# PCB-TLY-JACK.net
KiCad netlist of a schematic drawn in EAGLE
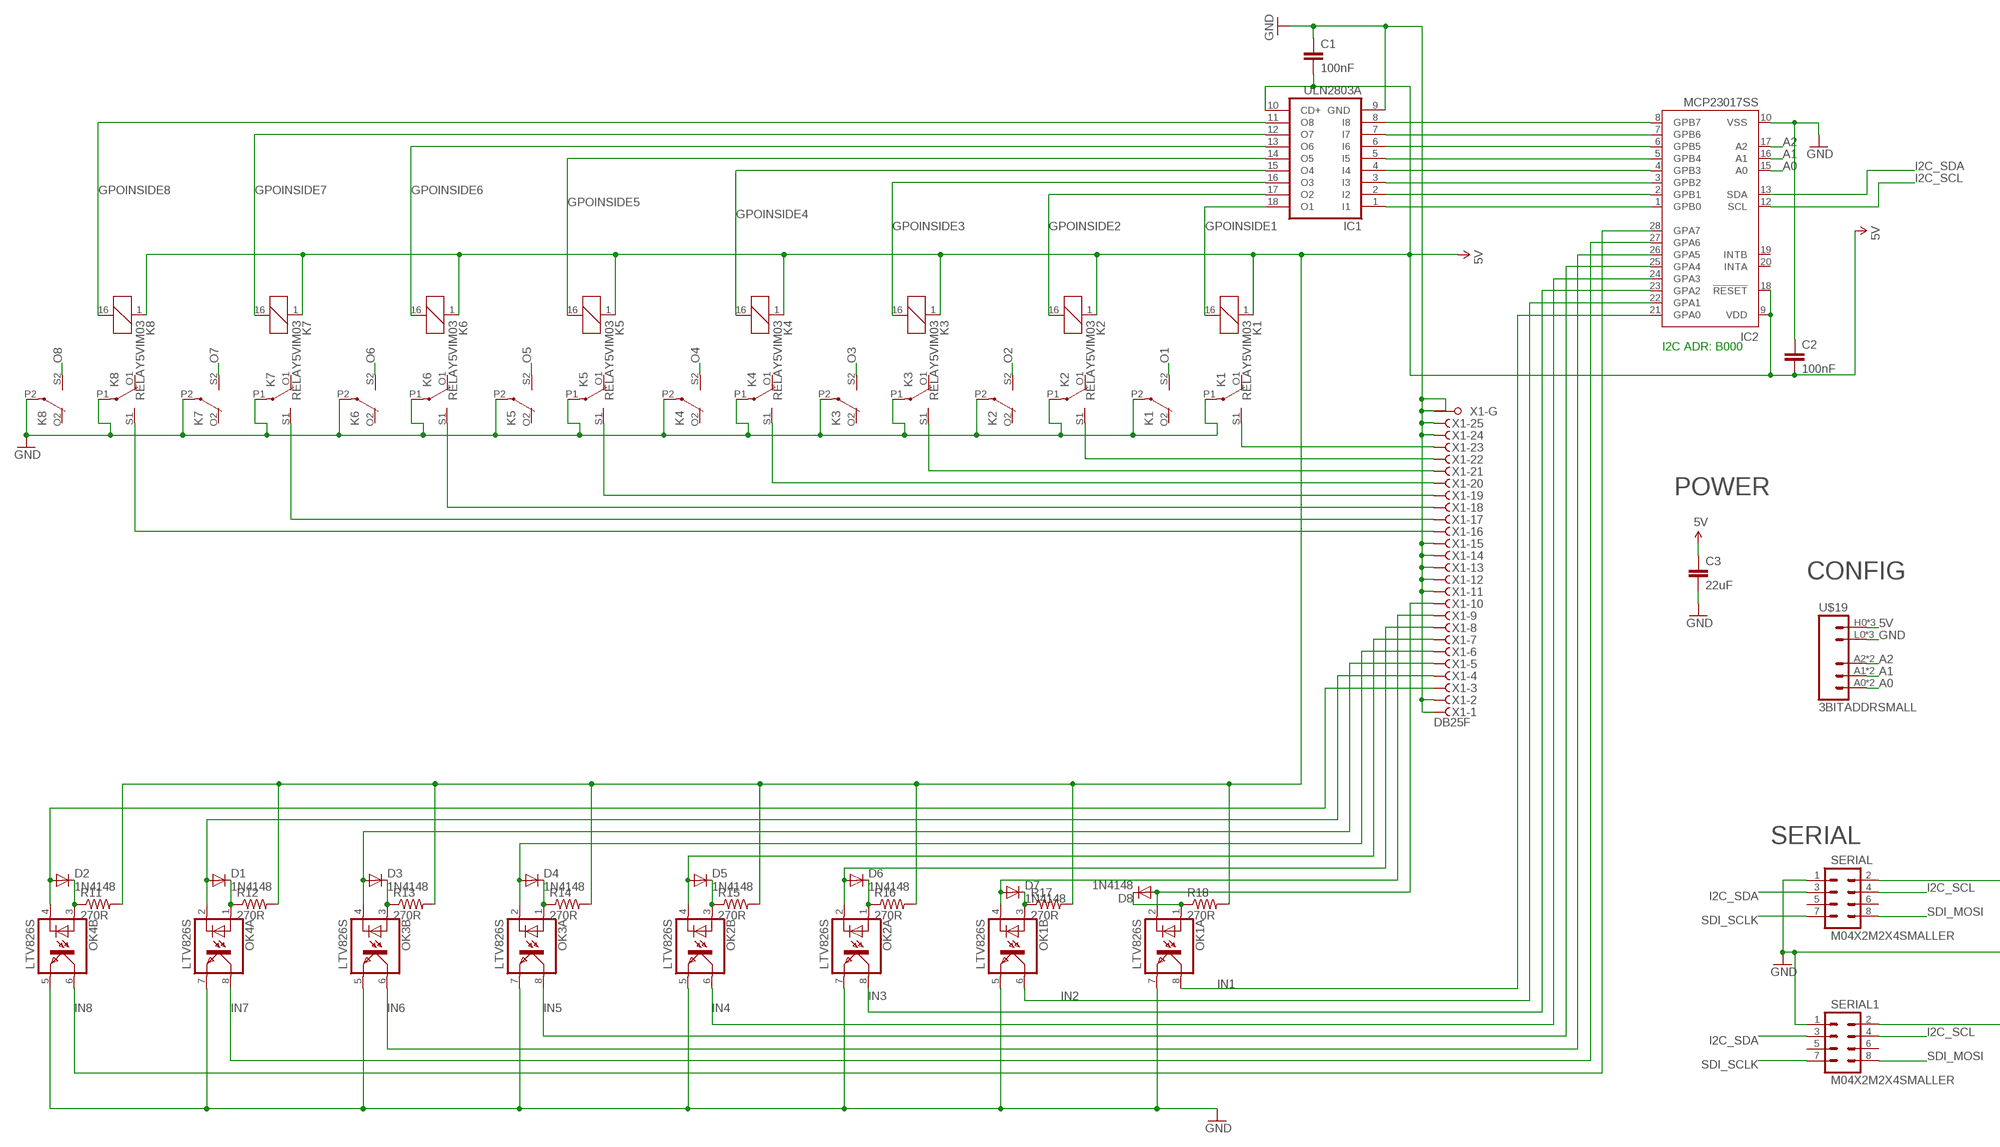
[diagram p0: schematic, sheet 1, part 1 of 2]
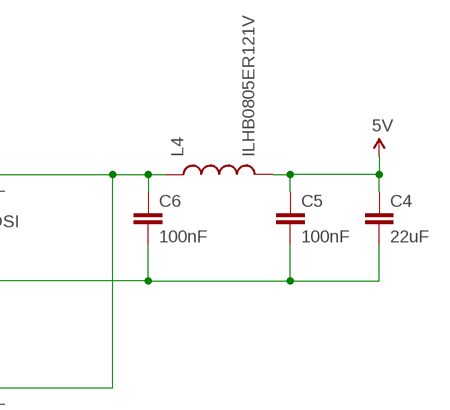
[diagram p1: schematic, sheet 1, part 2 of 2]

(export (version "E")
  (design (tool "Eeschema 10.0.6"))
  (components
    (comp (ref "C1")
      (value "100nF")
      (footprint "eagle-import:0603-CAP")
      (libsource (lib "eagle-import") (part "CAP0603-CAP"))
    )
    (comp (ref "C2")
      (value "100nF")
      (footprint "eagle-import:0603-CAP")
      (libsource (lib "eagle-import") (part "CAP0603-CAP"))
    )
    (comp (ref "C3")
      (value "22uF")
      (footprint "eagle-import:0805")
      (libsource (lib "eagle-import") (part "CAP0805"))
    )
    (comp (ref "C4")
      (value "22uF")
      (footprint "eagle-import:0805")
      (libsource (lib "eagle-import") (part "CAP0805"))
    )
    (comp (ref "C5")
      (value "100nF")
      (footprint "eagle-import:0603-CAP")
      (libsource (lib "eagle-import") (part "CAP0603-CAP"))
    )
    (comp (ref "C6")
      (value "100nF")
      (footprint "eagle-import:0603-CAP")
      (libsource (lib "eagle-import") (part "CAP0603-CAP"))
    )
    (comp (ref "D1")
      (value "1N4148")
      (footprint "eagle-import:SOD-323")
      (libsource (lib "eagle-import") (part "DIODESOD"))
    )
    (comp (ref "D2")
      (value "1N4148")
      (footprint "eagle-import:SOD-323")
      (libsource (lib "eagle-import") (part "DIODESOD"))
    )
    (comp (ref "D3")
      (value "1N4148")
      (footprint "eagle-import:SOD-323")
      (libsource (lib "eagle-import") (part "DIODESOD"))
    )
    (comp (ref "D4")
      (value "1N4148")
      (footprint "eagle-import:SOD-323")
      (libsource (lib "eagle-import") (part "DIODESOD"))
    )
    (comp (ref "D5")
      (value "1N4148")
      (footprint "eagle-import:SOD-323")
      (libsource (lib "eagle-import") (part "DIODESOD"))
    )
    (comp (ref "D6")
      (value "1N4148")
      (footprint "eagle-import:SOD-323")
      (libsource (lib "eagle-import") (part "DIODESOD"))
    )
    (comp (ref "D7")
      (value "1N4148")
      (footprint "eagle-import:SOD-323")
      (libsource (lib "eagle-import") (part "DIODESOD"))
    )
    (comp (ref "D8")
      (value "1N4148")
      (footprint "eagle-import:SOD-323")
      (libsource (lib "eagle-import") (part "DIODESOD"))
    )
    (comp (ref "IC1")
      (value "ULN2803A")
      (footprint "eagle-import:SO18W")
      (libsource (lib "eagle-import") (part "ULN2803ASO18W"))
    )
    (comp (ref "IC2")
      (value "MCP23017SS")
      (footprint "eagle-import:SSOP28")
      (fields (field (name "MF") "MICROCHIP") (field (name "MPN") "MCP23017-E/SS"))
      (libsource (lib "eagle-import") (part "MCP23017SS"))
    )
    (comp (ref "K1")
      (value "RELAY5VIM03")
      (footprint "eagle-import:DS2Y")
      (libsource (lib "eagle-import") (part "RELAY5VIM03"))
    )
    (comp (ref "K2")
      (value "RELAY5VIM03")
      (footprint "eagle-import:DS2Y")
      (libsource (lib "eagle-import") (part "RELAY5VIM03"))
    )
    (comp (ref "K3")
      (value "RELAY5VIM03")
      (footprint "eagle-import:DS2Y")
      (libsource (lib "eagle-import") (part "RELAY5VIM03"))
    )
    (comp (ref "K4")
      (value "RELAY5VIM03")
      (footprint "eagle-import:DS2Y")
      (libsource (lib "eagle-import") (part "RELAY5VIM03"))
    )
    (comp (ref "K5")
      (value "RELAY5VIM03")
      (footprint "eagle-import:DS2Y")
      (libsource (lib "eagle-import") (part "RELAY5VIM03"))
    )
    (comp (ref "K6")
      (value "RELAY5VIM03")
      (footprint "eagle-import:DS2Y")
      (libsource (lib "eagle-import") (part "RELAY5VIM03"))
    )
    (comp (ref "K7")
      (value "RELAY5VIM03")
      (footprint "eagle-import:DS2Y")
      (libsource (lib "eagle-import") (part "RELAY5VIM03"))
    )
    (comp (ref "K8")
      (value "RELAY5VIM03")
      (footprint "eagle-import:DS2Y")
      (libsource (lib "eagle-import") (part "RELAY5VIM03"))
    )
    (comp (ref "L4")
      (value "ILHB0805ER121V")
      (footprint "eagle-import:0805")
      (libsource (lib "eagle-import") (part "INDUCTOR0805"))
    )
    (comp (ref "OK1")
      (value "LTV826S")
      (footprint "eagle-import:DIL8-SMD")
      (libsource (lib "eagle-import") (part "LTV826S"))
    )
    (comp (ref "OK2")
      (value "LTV826S")
      (footprint "eagle-import:DIL8-SMD")
      (libsource (lib "eagle-import") (part "LTV826S"))
    )
    (comp (ref "OK3")
      (value "LTV826S")
      (footprint "eagle-import:DIL8-SMD")
      (libsource (lib "eagle-import") (part "LTV826S"))
    )
    (comp (ref "OK4")
      (value "LTV826S")
      (footprint "eagle-import:DIL8-SMD")
      (libsource (lib "eagle-import") (part "LTV826S"))
    )
    (comp (ref "R11")
      (value "270R")
      (footprint "eagle-import:0603-RES")
      (libsource (lib "eagle-import") (part "RESISTOR0603-RES"))
    )
    (comp (ref "R12")
      (value "270R")
      (footprint "eagle-import:0603-RES")
      (libsource (lib "eagle-import") (part "RESISTOR0603-RES"))
    )
    (comp (ref "R13")
      (value "270R")
      (footprint "eagle-import:0603-RES")
      (libsource (lib "eagle-import") (part "RESISTOR0603-RES"))
    )
    (comp (ref "R14")
      (value "270R")
      (footprint "eagle-import:0603-RES")
      (libsource (lib "eagle-import") (part "RESISTOR0603-RES"))
    )
    (comp (ref "R15")
      (value "270R")
      (footprint "eagle-import:0603-RES")
      (libsource (lib "eagle-import") (part "RESISTOR0603-RES"))
    )
    (comp (ref "R16")
      (value "270R")
      (footprint "eagle-import:0603-RES")
      (libsource (lib "eagle-import") (part "RESISTOR0603-RES"))
    )
    (comp (ref "R17")
      (value "270R")
      (footprint "eagle-import:0603-RES")
      (libsource (lib "eagle-import") (part "RESISTOR0603-RES"))
    )
    (comp (ref "R18")
      (value "270R")
      (footprint "eagle-import:0603-RES")
      (libsource (lib "eagle-import") (part "RESISTOR0603-RES"))
    )
    (comp (ref "SERIAL")
      (value "M04X2M2X4SMALLER")
      (footprint "eagle-import:M2X4SMALLER")
      (libsource (lib "eagle-import") (part "M04X2M2X4SMALLER"))
    )
    (comp (ref "SERIAL1")
      (value "M04X2M2X4SMALLER")
      (footprint "eagle-import:M2X4SMALLER")
      (libsource (lib "eagle-import") (part "M04X2M2X4SMALLER"))
    )
    (comp (ref "U$19")
      (value "3BITADDRSMALL")
      (footprint "eagle-import:3BITADDR_SMALL")
      (libsource (lib "eagle-import") (part "3BITADDRSMALL"))
    )
    (comp (ref "X1")
      (value "DB25F")
      (footprint "eagle-import:F25HP")
      (libsource (lib "eagle-import") (part "F25HPS"))
    )
  )
  (nets
    (net (code "1") (name "5V") (class "Default")
      (node (ref "C1") (pin "2") (pinfunction "2_2") (pintype "passive"))
      (node (ref "C2") (pin "2") (pinfunction "2_2") (pintype "passive"))
      (node (ref "C3") (pin "1") (pinfunction "1_1") (pintype "passive"))
      (node (ref "C4") (pin "1") (pinfunction "1_1") (pintype "passive"))
      (node (ref "C5") (pin "1") (pinfunction "1_1") (pintype "passive"))
      (node (ref "IC1") (pin "10") (pinfunction "CD+_10") (pintype "passive"))
      (node (ref "IC2") (pin "18") (pinfunction "~{RESET}_18") (pintype "input"))
      (node (ref "IC2") (pin "9") (pinfunction "VDD_9") (pintype "power_in"))
      (node (ref "K1") (pin "1") (pinfunction "1_1") (pintype "passive"))
      (node (ref "K2") (pin "1") (pinfunction "1_1") (pintype "passive"))
      (node (ref "K3") (pin "1") (pinfunction "1_1") (pintype "passive"))
      (node (ref "K4") (pin "1") (pinfunction "1_1") (pintype "passive"))
      (node (ref "K5") (pin "1") (pinfunction "1_1") (pintype "passive"))
      (node (ref "K6") (pin "1") (pinfunction "1_1") (pintype "passive"))
      (node (ref "K7") (pin "1") (pinfunction "1_1") (pintype "passive"))
      (node (ref "K8") (pin "1") (pinfunction "1_1") (pintype "passive"))
      (node (ref "L4") (pin "2") (pinfunction "2_2") (pintype "passive"))
      (node (ref "R11") (pin "2") (pinfunction "2_2") (pintype "passive"))
      (node (ref "R12") (pin "2") (pinfunction "2_2") (pintype "passive"))
      (node (ref "R13") (pin "2") (pinfunction "2_2") (pintype "passive"))
      (node (ref "R14") (pin "2") (pinfunction "2_2") (pintype "passive"))
      (node (ref "R15") (pin "2") (pinfunction "2_2") (pintype "passive"))
      (node (ref "R16") (pin "2") (pinfunction "2_2") (pintype "passive"))
      (node (ref "R17") (pin "2") (pinfunction "2_2") (pintype "passive"))
      (node (ref "R18") (pin "2") (pinfunction "2_2") (pintype "passive"))
      (node (ref "U$19") (pin "H0") (pinfunction "VCC_H0") (pintype "passive"))
      (node (ref "U$19") (pin "H1") (pinfunction "VCC_H1") (pintype "passive"))
      (node (ref "U$19") (pin "H2") (pinfunction "VCC_H2") (pintype "passive"))
    )
    (net (code "2") (name "A0") (class "Default")
      (node (ref "IC2") (pin "15") (pinfunction "A0_15") (pintype "input"))
      (node (ref "U$19") (pin "A0") (pinfunction "A0_A0") (pintype "passive"))
      (node (ref "U$19") (pin "AS0") (pinfunction "A0_AS0") (pintype "passive"))
    )
    (net (code "3") (name "A1") (class "Default")
      (node (ref "IC2") (pin "16") (pinfunction "A1_16") (pintype "input"))
      (node (ref "U$19") (pin "A1") (pinfunction "A1_A1") (pintype "passive"))
      (node (ref "U$19") (pin "AS1") (pinfunction "A1_AS1") (pintype "passive"))
    )
    (net (code "4") (name "A2") (class "Default")
      (node (ref "IC2") (pin "17") (pinfunction "A2_17") (pintype "input"))
      (node (ref "U$19") (pin "A2") (pinfunction "A2_A2") (pintype "passive"))
      (node (ref "U$19") (pin "AS2") (pinfunction "A2_AS2") (pintype "passive"))
    )
    (net (code "5") (name "GND") (class "Default")
      (node (ref "C1") (pin "1") (pinfunction "1_1") (pintype "passive"))
      (node (ref "C2") (pin "1") (pinfunction "1_1") (pintype "passive"))
      (node (ref "C3") (pin "2") (pinfunction "2_2") (pintype "passive"))
      (node (ref "C4") (pin "2") (pinfunction "2_2") (pintype "passive"))
      (node (ref "C5") (pin "2") (pinfunction "2_2") (pintype "passive"))
      (node (ref "C6") (pin "2") (pinfunction "2_2") (pintype "passive"))
      (node (ref "IC1") (pin "9") (pinfunction "GND_9") (pintype "power_in"))
      (node (ref "IC2") (pin "10") (pinfunction "VSS_10") (pintype "power_in"))
      (node (ref "K1") (pin "P1") (pinfunction "P_P1") (pintype "passive"))
      (node (ref "K1") (pin "P2") (pinfunction "P_P2") (pintype "passive"))
      (node (ref "K2") (pin "P1") (pinfunction "P_P1") (pintype "passive"))
      (node (ref "K2") (pin "P2") (pinfunction "P_P2") (pintype "passive"))
      (node (ref "K3") (pin "P1") (pinfunction "P_P1") (pintype "passive"))
      (node (ref "K3") (pin "P2") (pinfunction "P_P2") (pintype "passive"))
      (node (ref "K4") (pin "P1") (pinfunction "P_P1") (pintype "passive"))
      (node (ref "K4") (pin "P2") (pinfunction "P_P2") (pintype "passive"))
      (node (ref "K5") (pin "P1") (pinfunction "P_P1") (pintype "passive"))
      (node (ref "K5") (pin "P2") (pinfunction "P_P2") (pintype "passive"))
      (node (ref "K6") (pin "P1") (pinfunction "P_P1") (pintype "passive"))
      (node (ref "K6") (pin "P2") (pinfunction "P_P2") (pintype "passive"))
      (node (ref "K7") (pin "P1") (pinfunction "P_P1") (pintype "passive"))
      (node (ref "K7") (pin "P2") (pinfunction "P_P2") (pintype "passive"))
      (node (ref "K8") (pin "P1") (pinfunction "P_P1") (pintype "passive"))
      (node (ref "K8") (pin "P2") (pinfunction "P_P2") (pintype "passive"))
      (node (ref "OK1") (pin "5") (pinfunction "EMIT_5") (pintype "passive"))
      (node (ref "OK1") (pin "7") (pinfunction "EMIT_7") (pintype "passive"))
      (node (ref "OK2") (pin "5") (pinfunction "EMIT_5") (pintype "passive"))
      (node (ref "OK2") (pin "7") (pinfunction "EMIT_7") (pintype "passive"))
      (node (ref "OK3") (pin "5") (pinfunction "EMIT_5") (pintype "passive"))
      (node (ref "OK3") (pin "7") (pinfunction "EMIT_7") (pintype "passive"))
      (node (ref "OK4") (pin "5") (pinfunction "EMIT_5") (pintype "passive"))
      (node (ref "OK4") (pin "7") (pinfunction "EMIT_7") (pintype "passive"))
      (node (ref "SERIAL") (pin "1") (pinfunction "1_1") (pintype "passive"))
      (node (ref "SERIAL1") (pin "1") (pinfunction "1_1") (pintype "passive"))
      (node (ref "U$19") (pin "L0") (pinfunction "GND_L0") (pintype "passive"))
      (node (ref "U$19") (pin "L1") (pinfunction "GND_L1") (pintype "passive"))
      (node (ref "U$19") (pin "L2") (pinfunction "GND_L2") (pintype "passive"))
      (node (ref "X1") (pin "1") (pinfunction "F_1") (pintype "passive"))
      (node (ref "X1") (pin "11") (pinfunction "F_11") (pintype "passive"))
      (node (ref "X1") (pin "12") (pinfunction "F_12") (pintype "passive"))
      (node (ref "X1") (pin "13") (pinfunction "F_13") (pintype "passive"))
      (node (ref "X1") (pin "14") (pinfunction "F_14") (pintype "passive"))
      (node (ref "X1") (pin "15") (pinfunction "F_15") (pintype "passive"))
      (node (ref "X1") (pin "2") (pinfunction "F_2") (pintype "passive"))
      (node (ref "X1") (pin "24") (pinfunction "F_24") (pintype "passive"))
      (node (ref "X1") (pin "25") (pinfunction "F_25") (pintype "passive"))
      (node (ref "X1") (pin "G1") (pinfunction "G1_G1") (pintype "passive"))
      (node (ref "X1") (pin "G2") (pinfunction "G2_G2") (pintype "passive"))
    )
    (net (code "6") (name "GPOINSIDE1") (class "Default")
      (node (ref "IC1") (pin "18") (pinfunction "O1_18") (pintype "open_collector"))
      (node (ref "K1") (pin "16") (pinfunction "2_16") (pintype "passive"))
    )
    (net (code "7") (name "GPOINSIDE2") (class "Default")
      (node (ref "IC1") (pin "17") (pinfunction "O2_17") (pintype "open_collector"))
      (node (ref "K2") (pin "16") (pinfunction "2_16") (pintype "passive"))
    )
    (net (code "8") (name "GPOINSIDE3") (class "Default")
      (node (ref "IC1") (pin "16") (pinfunction "O3_16") (pintype "open_collector"))
      (node (ref "K3") (pin "16") (pinfunction "2_16") (pintype "passive"))
    )
    (net (code "9") (name "GPOINSIDE4") (class "Default")
      (node (ref "IC1") (pin "15") (pinfunction "O4_15") (pintype "open_collector"))
      (node (ref "K4") (pin "16") (pinfunction "2_16") (pintype "passive"))
    )
    (net (code "10") (name "GPOINSIDE5") (class "Default")
      (node (ref "IC1") (pin "14") (pinfunction "O5_14") (pintype "open_collector"))
      (node (ref "K5") (pin "16") (pinfunction "2_16") (pintype "passive"))
    )
    (net (code "11") (name "GPOINSIDE6") (class "Default")
      (node (ref "IC1") (pin "13") (pinfunction "O6_13") (pintype "open_collector"))
      (node (ref "K6") (pin "16") (pinfunction "2_16") (pintype "passive"))
    )
    (net (code "12") (name "GPOINSIDE7") (class "Default")
      (node (ref "IC1") (pin "12") (pinfunction "O7_12") (pintype "open_collector"))
      (node (ref "K7") (pin "16") (pinfunction "2_16") (pintype "passive"))
    )
    (net (code "13") (name "GPOINSIDE8") (class "Default")
      (node (ref "IC1") (pin "11") (pinfunction "O8_11") (pintype "open_collector"))
      (node (ref "K8") (pin "16") (pinfunction "2_16") (pintype "passive"))
    )
    (net (code "14") (name "I2C_SCL") (class "Default")
      (node (ref "IC2") (pin "12") (pinfunction "SCL_12") (pintype "input"))
      (node (ref "SERIAL") (pin "4") (pinfunction "4_4") (pintype "passive"))
      (node (ref "SERIAL1") (pin "4") (pinfunction "4_4") (pintype "passive"))
    )
    (net (code "15") (name "I2C_SDA") (class "Default")
      (node (ref "IC2") (pin "13") (pinfunction "SDA_13") (pintype "bidirectional"))
      (node (ref "SERIAL") (pin "3") (pinfunction "3_3") (pintype "passive"))
      (node (ref "SERIAL1") (pin "3") (pinfunction "3_3") (pintype "passive"))
    )
    (net (code "16") (name "IN1") (class "Default")
      (node (ref "IC2") (pin "21") (pinfunction "GPA0_21") (pintype "bidirectional"))
      (node (ref "OK1") (pin "8") (pinfunction "COL_8") (pintype "passive"))
    )
    (net (code "17") (name "IN2") (class "Default")
      (node (ref "IC2") (pin "22") (pinfunction "GPA1_22") (pintype "bidirectional"))
      (node (ref "OK1") (pin "6") (pinfunction "COL_6") (pintype "passive"))
    )
    (net (code "18") (name "IN3") (class "Default")
      (node (ref "IC2") (pin "23") (pinfunction "GPA2_23") (pintype "bidirectional"))
      (node (ref "OK2") (pin "8") (pinfunction "COL_8") (pintype "passive"))
    )
    (net (code "19") (name "IN4") (class "Default")
      (node (ref "IC2") (pin "24") (pinfunction "GPA3_24") (pintype "bidirectional"))
      (node (ref "OK2") (pin "6") (pinfunction "COL_6") (pintype "passive"))
    )
    (net (code "20") (name "IN5") (class "Default")
      (node (ref "IC2") (pin "25") (pinfunction "GPA4_25") (pintype "bidirectional"))
      (node (ref "OK3") (pin "8") (pinfunction "COL_8") (pintype "passive"))
    )
    (net (code "21") (name "IN6") (class "Default")
      (node (ref "IC2") (pin "26") (pinfunction "GPA5_26") (pintype "bidirectional"))
      (node (ref "OK3") (pin "6") (pinfunction "COL_6") (pintype "passive"))
    )
    (net (code "22") (name "IN7") (class "Default")
      (node (ref "IC2") (pin "27") (pinfunction "GPA6_27") (pintype "bidirectional"))
      (node (ref "OK4") (pin "8") (pinfunction "COL_8") (pintype "passive"))
    )
    (net (code "23") (name "IN8") (class "Default")
      (node (ref "IC2") (pin "28") (pinfunction "GPA7_28") (pintype "bidirectional"))
      (node (ref "OK4") (pin "6") (pinfunction "COL_6") (pintype "passive"))
    )
    (net (code "24") (name "Net-(C6-Pad1)") (class "Default")
      (node (ref "C6") (pin "1") (pinfunction "1_1") (pintype "passive"))
      (node (ref "L4") (pin "1") (pinfunction "1_1") (pintype "passive"))
      (node (ref "SERIAL") (pin "2") (pinfunction "2_2") (pintype "passive"))
      (node (ref "SERIAL1") (pin "2") (pinfunction "2_2") (pintype "passive"))
    )
    (net (code "25") (name "Net-(D1-A)") (class "Default")
      (node (ref "D1") (pin "2") (pinfunction "A_2") (pintype "passive"))
      (node (ref "OK4") (pin "2") (pinfunction "C_2") (pintype "passive"))
      (node (ref "X1") (pin "4") (pinfunction "F_4") (pintype "passive"))
    )
    (net (code "26") (name "Net-(D1-C)") (class "Default")
      (node (ref "D1") (pin "1") (pinfunction "C_1") (pintype "passive"))
      (node (ref "OK4") (pin "1") (pinfunction "A_1") (pintype "passive"))
      (node (ref "R12") (pin "1") (pinfunction "1_1") (pintype "passive"))
    )
    (net (code "27") (name "Net-(D2-A)") (class "Default")
      (node (ref "D2") (pin "2") (pinfunction "A_2") (pintype "passive"))
      (node (ref "OK4") (pin "4") (pinfunction "C_4") (pintype "passive"))
      (node (ref "X1") (pin "3") (pinfunction "F_3") (pintype "passive"))
    )
    (net (code "28") (name "Net-(D2-C)") (class "Default")
      (node (ref "D2") (pin "1") (pinfunction "C_1") (pintype "passive"))
      (node (ref "OK4") (pin "3") (pinfunction "A_3") (pintype "passive"))
      (node (ref "R11") (pin "1") (pinfunction "1_1") (pintype "passive"))
    )
    (net (code "29") (name "Net-(D3-A)") (class "Default")
      (node (ref "D3") (pin "2") (pinfunction "A_2") (pintype "passive"))
      (node (ref "OK3") (pin "4") (pinfunction "C_4") (pintype "passive"))
      (node (ref "X1") (pin "5") (pinfunction "F_5") (pintype "passive"))
    )
    (net (code "30") (name "Net-(D3-C)") (class "Default")
      (node (ref "D3") (pin "1") (pinfunction "C_1") (pintype "passive"))
      (node (ref "OK3") (pin "3") (pinfunction "A_3") (pintype "passive"))
      (node (ref "R13") (pin "1") (pinfunction "1_1") (pintype "passive"))
    )
    (net (code "31") (name "Net-(D4-A)") (class "Default")
      (node (ref "D4") (pin "2") (pinfunction "A_2") (pintype "passive"))
      (node (ref "OK3") (pin "2") (pinfunction "C_2") (pintype "passive"))
      (node (ref "X1") (pin "6") (pinfunction "F_6") (pintype "passive"))
    )
    (net (code "32") (name "Net-(D4-C)") (class "Default")
      (node (ref "D4") (pin "1") (pinfunction "C_1") (pintype "passive"))
      (node (ref "OK3") (pin "1") (pinfunction "A_1") (pintype "passive"))
      (node (ref "R14") (pin "1") (pinfunction "1_1") (pintype "passive"))
    )
    (net (code "33") (name "Net-(D5-A)") (class "Default")
      (node (ref "D5") (pin "2") (pinfunction "A_2") (pintype "passive"))
      (node (ref "OK2") (pin "4") (pinfunction "C_4") (pintype "passive"))
      (node (ref "X1") (pin "7") (pinfunction "F_7") (pintype "passive"))
    )
    (net (code "34") (name "Net-(D5-C)") (class "Default")
      (node (ref "D5") (pin "1") (pinfunction "C_1") (pintype "passive"))
      (node (ref "OK2") (pin "3") (pinfunction "A_3") (pintype "passive"))
      (node (ref "R15") (pin "1") (pinfunction "1_1") (pintype "passive"))
    )
    (net (code "35") (name "Net-(D6-A)") (class "Default")
      (node (ref "D6") (pin "2") (pinfunction "A_2") (pintype "passive"))
      (node (ref "OK2") (pin "2") (pinfunction "C_2") (pintype "passive"))
      (node (ref "X1") (pin "8") (pinfunction "F_8") (pintype "passive"))
    )
    (net (code "36") (name "Net-(D6-C)") (class "Default")
      (node (ref "D6") (pin "1") (pinfunction "C_1") (pintype "passive"))
      (node (ref "OK2") (pin "1") (pinfunction "A_1") (pintype "passive"))
      (node (ref "R16") (pin "1") (pinfunction "1_1") (pintype "passive"))
    )
    (net (code "37") (name "Net-(D7-A)") (class "Default")
      (node (ref "D7") (pin "2") (pinfunction "A_2") (pintype "passive"))
      (node (ref "OK1") (pin "4") (pinfunction "C_4") (pintype "passive"))
      (node (ref "X1") (pin "9") (pinfunction "F_9") (pintype "passive"))
    )
    (net (code "38") (name "Net-(D7-C)") (class "Default")
      (node (ref "D7") (pin "1") (pinfunction "C_1") (pintype "passive"))
      (node (ref "OK1") (pin "3") (pinfunction "A_3") (pintype "passive"))
      (node (ref "R17") (pin "1") (pinfunction "1_1") (pintype "passive"))
    )
    (net (code "39") (name "Net-(D8-A)") (class "Default")
      (node (ref "D8") (pin "2") (pinfunction "A_2") (pintype "passive"))
      (node (ref "OK1") (pin "2") (pinfunction "C_2") (pintype "passive"))
      (node (ref "X1") (pin "10") (pinfunction "F_10") (pintype "passive"))
    )
    (net (code "40") (name "Net-(D8-C)") (class "Default")
      (node (ref "D8") (pin "1") (pinfunction "C_1") (pintype "passive"))
      (node (ref "OK1") (pin "1") (pinfunction "A_1") (pintype "passive"))
      (node (ref "R18") (pin "1") (pinfunction "1_1") (pintype "passive"))
    )
    (net (code "41") (name "Net-(IC1-I1)") (class "Default")
      (node (ref "IC1") (pin "1") (pinfunction "I1_1") (pintype "input"))
      (node (ref "IC2") (pin "1") (pinfunction "GPB0_1") (pintype "bidirectional"))
    )
    (net (code "42") (name "Net-(IC1-I2)") (class "Default")
      (node (ref "IC1") (pin "2") (pinfunction "I2_2") (pintype "input"))
      (node (ref "IC2") (pin "2") (pinfunction "GPB1_2") (pintype "bidirectional"))
    )
    (net (code "43") (name "Net-(IC1-I3)") (class "Default")
      (node (ref "IC1") (pin "3") (pinfunction "I3_3") (pintype "input"))
      (node (ref "IC2") (pin "3") (pinfunction "GPB2_3") (pintype "bidirectional"))
    )
    (net (code "44") (name "Net-(IC1-I4)") (class "Default")
      (node (ref "IC1") (pin "4") (pinfunction "I4_4") (pintype "input"))
      (node (ref "IC2") (pin "4") (pinfunction "GPB3_4") (pintype "bidirectional"))
    )
    (net (code "45") (name "Net-(IC1-I5)") (class "Default")
      (node (ref "IC1") (pin "5") (pinfunction "I5_5") (pintype "input"))
      (node (ref "IC2") (pin "5") (pinfunction "GPB4_5") (pintype "bidirectional"))
    )
    (net (code "46") (name "Net-(IC1-I6)") (class "Default")
      (node (ref "IC1") (pin "6") (pinfunction "I6_6") (pintype "input"))
      (node (ref "IC2") (pin "6") (pinfunction "GPB5_6") (pintype "bidirectional"))
    )
    (net (code "47") (name "Net-(IC1-I7)") (class "Default")
      (node (ref "IC1") (pin "7") (pinfunction "I7_7") (pintype "input"))
      (node (ref "IC2") (pin "7") (pinfunction "GPB6_7") (pintype "bidirectional"))
    )
    (net (code "48") (name "Net-(IC1-I8)") (class "Default")
      (node (ref "IC1") (pin "8") (pinfunction "I8_8") (pintype "input"))
      (node (ref "IC2") (pin "8") (pinfunction "GPB7_8") (pintype "bidirectional"))
    )
    (net (code "49") (name "Net-(K1B-S)") (class "Default")
      (node (ref "K1") (pin "S1") (pinfunction "S_S1") (pintype "passive"))
      (node (ref "X1") (pin "23") (pinfunction "F_23") (pintype "passive"))
    )
    (net (code "50") (name "Net-(K2B-S)") (class "Default")
      (node (ref "K2") (pin "S1") (pinfunction "S_S1") (pintype "passive"))
      (node (ref "X1") (pin "22") (pinfunction "F_22") (pintype "passive"))
    )
    (net (code "51") (name "Net-(K3B-S)") (class "Default")
      (node (ref "K3") (pin "S1") (pinfunction "S_S1") (pintype "passive"))
      (node (ref "X1") (pin "21") (pinfunction "F_21") (pintype "passive"))
    )
    (net (code "52") (name "Net-(K4B-S)") (class "Default")
      (node (ref "K4") (pin "S1") (pinfunction "S_S1") (pintype "passive"))
      (node (ref "X1") (pin "20") (pinfunction "F_20") (pintype "passive"))
    )
    (net (code "53") (name "Net-(K5B-S)") (class "Default")
      (node (ref "K5") (pin "S1") (pinfunction "S_S1") (pintype "passive"))
      (node (ref "X1") (pin "19") (pinfunction "F_19") (pintype "passive"))
    )
    (net (code "54") (name "Net-(K6B-S)") (class "Default")
      (node (ref "K6") (pin "S1") (pinfunction "S_S1") (pintype "passive"))
      (node (ref "X1") (pin "18") (pinfunction "F_18") (pintype "passive"))
    )
    (net (code "55") (name "Net-(K7B-S)") (class "Default")
      (node (ref "K7") (pin "S1") (pinfunction "S_S1") (pintype "passive"))
      (node (ref "X1") (pin "17") (pinfunction "F_17") (pintype "passive"))
    )
    (net (code "56") (name "Net-(K8B-S)") (class "Default")
      (node (ref "K8") (pin "S1") (pinfunction "S_S1") (pintype "passive"))
      (node (ref "X1") (pin "16") (pinfunction "F_16") (pintype "passive"))
    )
    (net (code "57") (name "O1") (class "Default")
      (node (ref "K1") (pin "S2") (pinfunction "S_S2") (pintype "passive"))
    )
    (net (code "58") (name "O2") (class "Default")
      (node (ref "K2") (pin "S2") (pinfunction "S_S2") (pintype "passive"))
    )
    (net (code "59") (name "O3") (class "Default")
      (node (ref "K3") (pin "S2") (pinfunction "S_S2") (pintype "passive"))
    )
    (net (code "60") (name "O4") (class "Default")
      (node (ref "K4") (pin "S2") (pinfunction "S_S2") (pintype "passive"))
    )
    (net (code "61") (name "O5") (class "Default")
      (node (ref "K5") (pin "S2") (pinfunction "S_S2") (pintype "passive"))
    )
    (net (code "62") (name "O6") (class "Default")
      (node (ref "K6") (pin "S2") (pinfunction "S_S2") (pintype "passive"))
    )
    (net (code "63") (name "O7") (class "Default")
      (node (ref "K7") (pin "S2") (pinfunction "S_S2") (pintype "passive"))
    )
    (net (code "64") (name "O8") (class "Default")
      (node (ref "K8") (pin "S2") (pinfunction "S_S2") (pintype "passive"))
    )
    (net (code "65") (name "SDI_MOSI") (class "Default")
      (node (ref "SERIAL") (pin "8") (pinfunction "8_8") (pintype "passive"))
      (node (ref "SERIAL1") (pin "8") (pinfunction "8_8") (pintype "passive"))
    )
    (net (code "66") (name "SDI_SCLK") (class "Default")
      (node (ref "SERIAL") (pin "7") (pinfunction "7_7") (pintype "passive"))
      (node (ref "SERIAL1") (pin "7") (pinfunction "7_7") (pintype "passive"))
    )
    (net (code "67") (name "unconnected-(IC2-INTA-Pad20)") (class "Default")
      (node (ref "IC2") (pin "20") (pinfunction "INTA_20") (pintype "output"))
    )
    (net (code "68") (name "unconnected-(IC2-INTB-Pad19)") (class "Default")
      (node (ref "IC2") (pin "19") (pinfunction "INTB_19") (pintype "output"))
    )
    (net (code "69") (name "unconnected-(K1B-O-PadO1)") (class "Default")
      (node (ref "K1") (pin "O1") (pinfunction "O_O1") (pintype "passive"))
    )
    (net (code "70") (name "unconnected-(K1C-O-PadO2)") (class "Default")
      (node (ref "K1") (pin "O2") (pinfunction "O_O2") (pintype "passive"))
    )
    (net (code "71") (name "unconnected-(K2B-O-PadO1)") (class "Default")
      (node (ref "K2") (pin "O1") (pinfunction "O_O1") (pintype "passive"))
    )
    (net (code "72") (name "unconnected-(K2C-O-PadO2)") (class "Default")
      (node (ref "K2") (pin "O2") (pinfunction "O_O2") (pintype "passive"))
    )
    (net (code "73") (name "unconnected-(K3B-O-PadO1)") (class "Default")
      (node (ref "K3") (pin "O1") (pinfunction "O_O1") (pintype "passive"))
    )
    (net (code "74") (name "unconnected-(K3C-O-PadO2)") (class "Default")
      (node (ref "K3") (pin "O2") (pinfunction "O_O2") (pintype "passive"))
    )
    (net (code "75") (name "unconnected-(K4B-O-PadO1)") (class "Default")
      (node (ref "K4") (pin "O1") (pinfunction "O_O1") (pintype "passive"))
    )
    (net (code "76") (name "unconnected-(K4C-O-PadO2)") (class "Default")
      (node (ref "K4") (pin "O2") (pinfunction "O_O2") (pintype "passive"))
    )
    (net (code "77") (name "unconnected-(K5B-O-PadO1)") (class "Default")
      (node (ref "K5") (pin "O1") (pinfunction "O_O1") (pintype "passive"))
    )
    (net (code "78") (name "unconnected-(K5C-O-PadO2)") (class "Default")
      (node (ref "K5") (pin "O2") (pinfunction "O_O2") (pintype "passive"))
    )
    (net (code "79") (name "unconnected-(K6B-O-PadO1)") (class "Default")
      (node (ref "K6") (pin "O1") (pinfunction "O_O1") (pintype "passive"))
    )
    (net (code "80") (name "unconnected-(K6C-O-PadO2)") (class "Default")
      (node (ref "K6") (pin "O2") (pinfunction "O_O2") (pintype "passive"))
    )
    (net (code "81") (name "unconnected-(K7B-O-PadO1)") (class "Default")
      (node (ref "K7") (pin "O1") (pinfunction "O_O1") (pintype "passive"))
    )
    (net (code "82") (name "unconnected-(K7C-O-PadO2)") (class "Default")
      (node (ref "K7") (pin "O2") (pinfunction "O_O2") (pintype "passive"))
    )
    (net (code "83") (name "unconnected-(K8B-O-PadO1)") (class "Default")
      (node (ref "K8") (pin "O1") (pinfunction "O_O1") (pintype "passive"))
    )
    (net (code "84") (name "unconnected-(K8C-O-PadO2)") (class "Default")
      (node (ref "K8") (pin "O2") (pinfunction "O_O2") (pintype "passive"))
    )
    (net (code "85") (name "unconnected-(SERIAL-Pad5)") (class "Default")
      (node (ref "SERIAL") (pin "5") (pinfunction "5_5") (pintype "passive"))
    )
    (net (code "86") (name "unconnected-(SERIAL-Pad6)") (class "Default")
      (node (ref "SERIAL") (pin "6") (pinfunction "6_6") (pintype "passive"))
    )
    (net (code "87") (name "unconnected-(SERIAL1-Pad5)") (class "Default")
      (node (ref "SERIAL1") (pin "5") (pinfunction "5_5") (pintype "passive"))
    )
    (net (code "88") (name "unconnected-(SERIAL1-Pad6)") (class "Default")
      (node (ref "SERIAL1") (pin "6") (pinfunction "6_6") (pintype "passive"))
    )
  )
)
